# MATRIX_CLOCK.net
KiCad netlist of a schematic drawn in Altium Designer
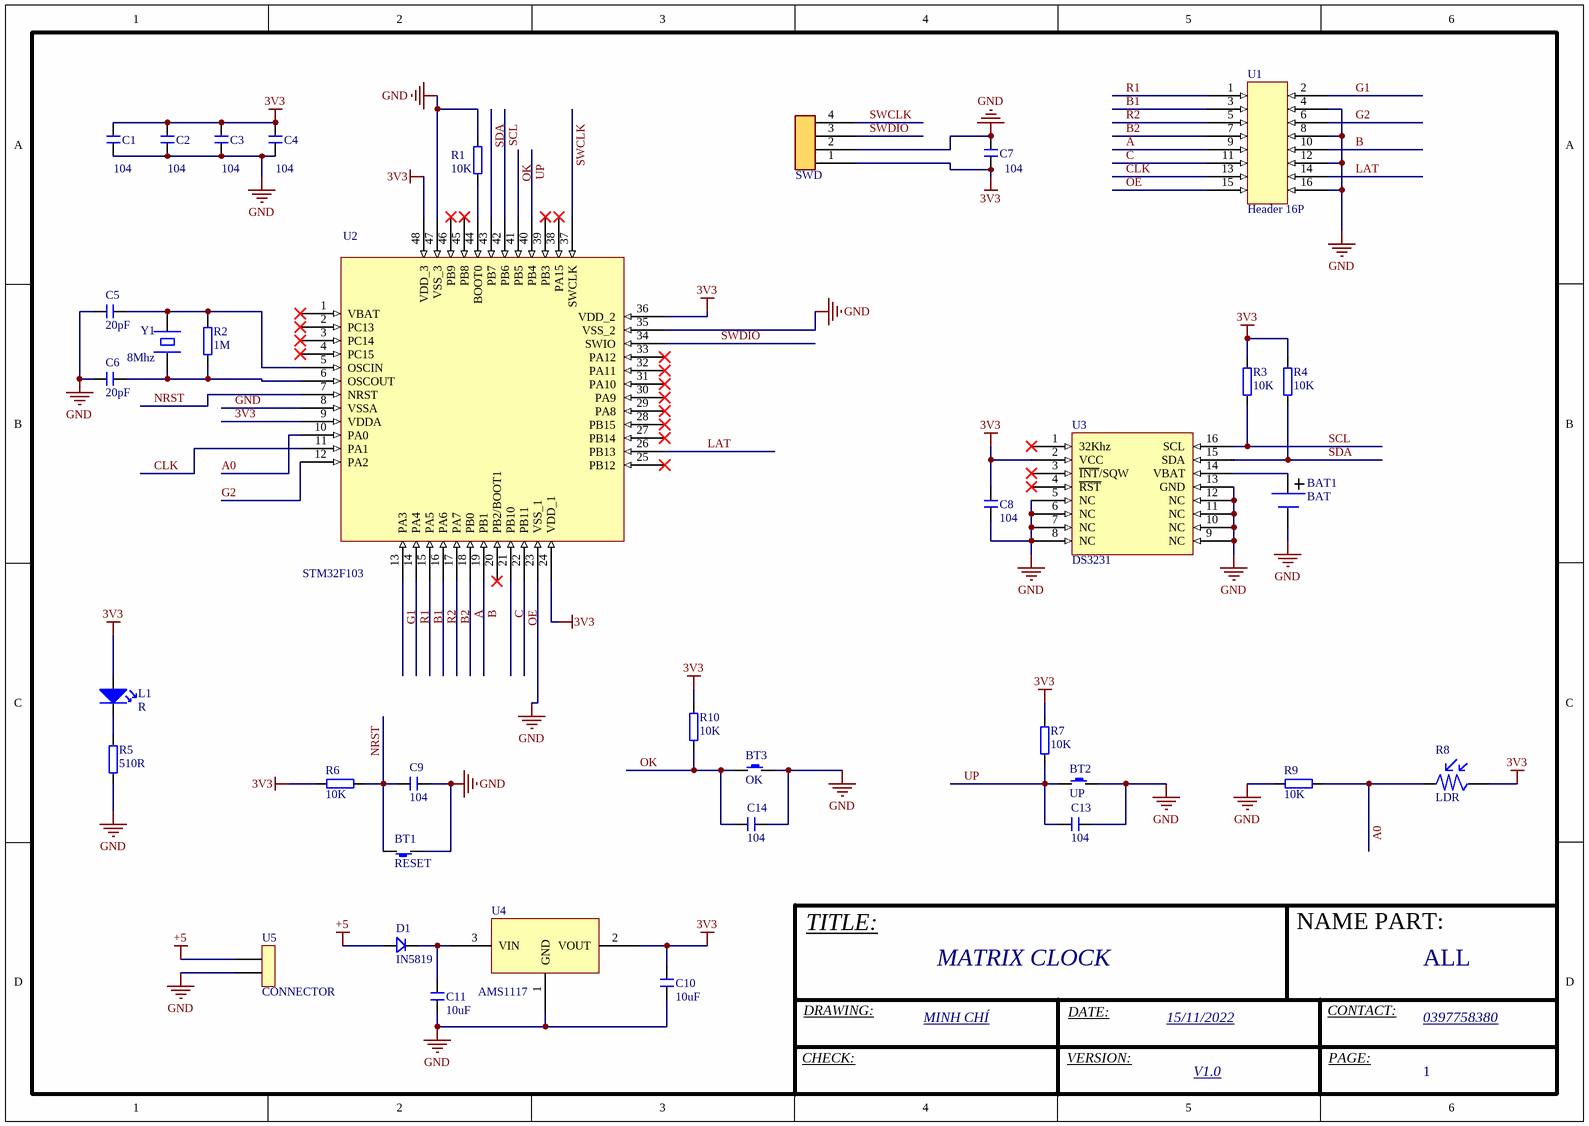
[diagram p0: MATRIX_CLOCK.SchDoc]

(export (version "E")
  (design (tool "Eeschema 10.0.6"))
  (components
    (comp (ref "BAT1")
      (value "BAT")
      (footprint "CR11220")
      (libsource (lib "Lib_MinhChi") (part "BAT_CR1220"))
    )
    (comp (ref "BT1")
      (value "RESET")
      (footprint "BUTTON-2P-SMD")
      (libsource (lib "Lib_MinhChi") (part "BUTON-2P"))
    )
    (comp (ref "BT2")
      (value "UP")
      (footprint "BUTTON-2P-SMD")
      (libsource (lib "Lib_MinhChi") (part "BUTON-2P"))
    )
    (comp (ref "BT3")
      (value "OK")
      (footprint "BUTTON-2P-SMD")
      (libsource (lib "Lib_MinhChi") (part "BUTON-2P"))
    )
    (comp (ref "C1") (value "104") (footprint "CAP-0805") (libsource (lib "Lib_MinhChi") (part "CAP-NON")))
    (comp (ref "C2") (value "104") (footprint "CAP-0805") (libsource (lib "Lib_MinhChi") (part "CAP-NON")))
    (comp (ref "C3") (value "104") (footprint "CAP-0805") (libsource (lib "Lib_MinhChi") (part "CAP-NON")))
    (comp (ref "C4") (value "104") (footprint "CAP-0805") (libsource (lib "Lib_MinhChi") (part "CAP-NON")))
    (comp (ref "C5") (value "20pF") (footprint "CAP-0805") (libsource (lib "Lib_MinhChi") (part "CAP-NON")))
    (comp (ref "C6") (value "20pF") (footprint "CAP-0805") (libsource (lib "Lib_MinhChi") (part "CAP-NON")))
    (comp (ref "C7") (value "104") (footprint "CAP-0805") (libsource (lib "Lib_MinhChi") (part "CAP-NON")))
    (comp (ref "C8") (value "104") (footprint "CAP-0805") (libsource (lib "Lib_MinhChi") (part "CAP-NON")))
    (comp (ref "C9") (value "104") (footprint "CAP-0805") (libsource (lib "Lib_MinhChi") (part "CAP-NON")))
    (comp (ref "C10") (value "10uF") (footprint "CAP-0805") (libsource (lib "Lib_MinhChi") (part "CAP-NON")))
    (comp (ref "C11") (value "10uF") (footprint "CAP-0805") (libsource (lib "Lib_MinhChi") (part "CAP-NON")))
    (comp (ref "C13") (value "104") (footprint "CAP-0805") (libsource (lib "Lib_MinhChi") (part "CAP-NON")))
    (comp (ref "C14") (value "104") (footprint "CAP-0805") (libsource (lib "Lib_MinhChi") (part "CAP-NON")))
    (comp (ref "D1") (value "IN5819") (footprint "IN5819") (libsource (lib "Lib_MinhChi") (part "DIODE")))
    (comp (ref "L1") (value "R") (footprint "LED-R") (libsource (lib "Lib_MinhChi") (part "LED-SINGLE")))
    (comp (ref "R1") (value "10K") (footprint "RES-0805") (libsource (lib "Lib_MinhChi") (part "RES")))
    (comp (ref "R2") (value "1M") (footprint "RES-0805") (libsource (lib "Lib_MinhChi") (part "RES")))
    (comp (ref "R3") (value "10K") (footprint "RES-0805") (libsource (lib "Lib_MinhChi") (part "RES")))
    (comp (ref "R4") (value "10K") (footprint "RES-0805") (libsource (lib "Lib_MinhChi") (part "RES")))
    (comp (ref "R5") (value "510R") (footprint "RES-0805") (libsource (lib "Lib_MinhChi") (part "RES")))
    (comp (ref "R6") (value "10K") (footprint "RES-0805") (libsource (lib "Lib_MinhChi") (part "RES")))
    (comp (ref "R7") (value "10K") (footprint "RES-0805") (libsource (lib "Lib_MinhChi") (part "RES")))
    (comp (ref "R8") (value "LDR") (footprint "LDR2") (libsource (lib "Lib_MinhChi") (part "LDR")))
    (comp (ref "R9") (value "10K") (footprint "RES-0805") (libsource (lib "Lib_MinhChi") (part "RES")))
    (comp (ref "R10") (value "10K") (footprint "RES-0805") (libsource (lib "Lib_MinhChi") (part "RES")))
    (comp (ref "SWD")
      (value "HEADER-4P")
      (footprint "HEADER-4P")
      (libsource (lib "Lib_MinhChi") (part "HEADER-4P"))
    )
    (comp (ref "U1")
      (value "Header 16P")
      (footprint "HEADER16P")
      (libsource (lib "Lib_MinhChi") (part "CONNECTOR 16P"))
    )
    (comp (ref "U2")
      (value "STM32F103")
      (footprint "LQFP-48")
      (libsource (lib "Lib_MinhChi") (part "STM32F103_MCU"))
    )
    (comp (ref "U3") (value "DS3231") (footprint "SOIC16-W") (libsource (lib "Lib_MinhChi") (part "DS3231")))
    (comp (ref "U4")
      (value "AMS1117")
      (footprint "SOT-223")
      (libsource (lib "Lib_MinhChi") (part "AMS1117_SOT-232"))
    )
    (comp (ref "U5") (value "CONNECTOR") (footprint "XH-2P") (libsource (lib "Lib_MinhChi") (part "XH-2P")))
    (comp (ref "Y1") (value "8Mhz") (footprint "QUARTZ") (libsource (lib "Lib_MinhChi") (part "Quartz")))
  )
  (nets
    (net (code "1") (name "+5") (class "Default")
      (node (ref "D1") (pin "1") (pinfunction "A_1") (pintype "passive"))
      (node (ref "U5") (pin "1") (pinfunction "1_1") (pintype "passive"))
    )
    (net (code "2") (name "/A") (class "Default")
      (node (ref "U1") (pin "9") (pintype "input"))
      (node (ref "U2") (pin "18") (pinfunction "PB0_18") (pintype "input"))
    )
    (net (code "3") (name "/A0") (class "Default")
      (node (ref "R8") (pin "1") (pinfunction "1_1") (pintype "passive"))
      (node (ref "R9") (pin "2") (pinfunction "2_2") (pintype "passive"))
      (node (ref "U2") (pin "10") (pinfunction "PA0_10") (pintype "input"))
    )
    (net (code "4") (name "/B") (class "Default")
      (node (ref "U1") (pin "10") (pintype "input"))
      (node (ref "U2") (pin "19") (pinfunction "PB1_19") (pintype "input"))
    )
    (net (code "5") (name "/B1") (class "Default")
      (node (ref "U1") (pin "3") (pintype "input"))
      (node (ref "U2") (pin "15") (pinfunction "PA5_15") (pintype "input"))
    )
    (net (code "6") (name "/B2") (class "Default")
      (node (ref "U1") (pin "7") (pintype "input"))
      (node (ref "U2") (pin "17") (pinfunction "PA7_17") (pintype "input"))
    )
    (net (code "7") (name "/C") (class "Default")
      (node (ref "U1") (pin "11") (pintype "input"))
      (node (ref "U2") (pin "21") (pinfunction "PB10_21") (pintype "input"))
    )
    (net (code "8") (name "/CLK") (class "Default")
      (node (ref "U1") (pin "13") (pintype "input"))
      (node (ref "U2") (pin "11") (pinfunction "PA1_11") (pintype "input"))
    )
    (net (code "9") (name "/G1") (class "Default")
      (node (ref "U1") (pin "2") (pintype "input"))
      (node (ref "U2") (pin "13") (pinfunction "PA3_13") (pintype "input"))
    )
    (net (code "10") (name "/G2") (class "Default")
      (node (ref "U1") (pin "6") (pintype "input"))
      (node (ref "U2") (pin "12") (pinfunction "PA2_12") (pintype "input"))
    )
    (net (code "11") (name "/LAT") (class "Default")
      (node (ref "U1") (pin "14") (pintype "input"))
      (node (ref "U2") (pin "26") (pinfunction "PB13_26") (pintype "input"))
    )
    (net (code "12") (name "/NRST") (class "Default")
      (node (ref "BT1") (pin "2") (pinfunction "2_2") (pintype "passive"))
      (node (ref "C9") (pin "1") (pinfunction "1_1") (pintype "passive"))
      (node (ref "R6") (pin "2") (pinfunction "2_2") (pintype "passive"))
      (node (ref "U2") (pin "7") (pinfunction "NRST_7") (pintype "input"))
    )
    (net (code "13") (name "/OE") (class "Default")
      (node (ref "U1") (pin "15") (pintype "input"))
      (node (ref "U2") (pin "22") (pinfunction "PB11_22") (pintype "input"))
    )
    (net (code "14") (name "/OK") (class "Default")
      (node (ref "BT3") (pin "1") (pinfunction "1_1") (pintype "passive"))
      (node (ref "C14") (pin "1") (pinfunction "1_1") (pintype "passive"))
      (node (ref "R10") (pin "2") (pinfunction "2_2") (pintype "passive"))
      (node (ref "U2") (pin "41") (pinfunction "PB5_41") (pintype "input"))
    )
    (net (code "15") (name "/R1") (class "Default")
      (node (ref "U1") (pin "1") (pintype "input"))
      (node (ref "U2") (pin "14") (pinfunction "PA4_14") (pintype "input"))
    )
    (net (code "16") (name "/R2") (class "Default")
      (node (ref "U1") (pin "5") (pintype "input"))
      (node (ref "U2") (pin "16") (pinfunction "PA6_16") (pintype "input"))
    )
    (net (code "17") (name "/SCL") (class "Default")
      (node (ref "R3") (pin "1") (pinfunction "1_1") (pintype "passive"))
      (node (ref "U2") (pin "42") (pinfunction "PB6_42") (pintype "input"))
      (node (ref "U3") (pin "16") (pinfunction "SCL_16") (pintype "input"))
    )
    (net (code "18") (name "/SDA") (class "Default")
      (node (ref "R4") (pin "1") (pinfunction "1_1") (pintype "passive"))
      (node (ref "U2") (pin "43") (pinfunction "PB7_43") (pintype "input"))
      (node (ref "U3") (pin "15") (pinfunction "SDA_15") (pintype "input"))
    )
    (net (code "19") (name "/SWCLK") (class "Default")
      (node (ref "SWD") (pin "4") (pinfunction "4_4") (pintype "passive"))
      (node (ref "U2") (pin "37") (pinfunction "SWCLK_37") (pintype "input"))
    )
    (net (code "20") (name "/SWDIO") (class "Default")
      (node (ref "SWD") (pin "3") (pinfunction "3_3") (pintype "passive"))
      (node (ref "U2") (pin "34") (pinfunction "SWIO_34") (pintype "input"))
    )
    (net (code "21") (name "/UP") (class "Default")
      (node (ref "BT2") (pin "1") (pinfunction "1_1") (pintype "passive"))
      (node (ref "C13") (pin "1") (pinfunction "1_1") (pintype "passive"))
      (node (ref "R7") (pin "2") (pinfunction "2_2") (pintype "passive"))
      (node (ref "U2") (pin "40") (pinfunction "PB4_40") (pintype "input"))
    )
    (net (code "22") (name "3V3") (class "Default")
      (node (ref "C1") (pin "1") (pinfunction "1_1") (pintype "passive"))
      (node (ref "C10") (pin "1") (pinfunction "1_1") (pintype "passive"))
      (node (ref "C2") (pin "1") (pinfunction "1_1") (pintype "passive"))
      (node (ref "C3") (pin "1") (pinfunction "1_1") (pintype "passive"))
      (node (ref "C4") (pin "1") (pinfunction "1_1") (pintype "passive"))
      (node (ref "C7") (pin "2") (pinfunction "2_2") (pintype "passive"))
      (node (ref "C8") (pin "1") (pinfunction "1_1") (pintype "passive"))
      (node (ref "L1") (pin "1") (pinfunction "1_1") (pintype "passive"))
      (node (ref "R10") (pin "1") (pinfunction "1_1") (pintype "passive"))
      (node (ref "R3") (pin "2") (pinfunction "2_2") (pintype "passive"))
      (node (ref "R4") (pin "2") (pinfunction "2_2") (pintype "passive"))
      (node (ref "R6") (pin "1") (pinfunction "1_1") (pintype "passive"))
      (node (ref "R7") (pin "1") (pinfunction "1_1") (pintype "passive"))
      (node (ref "R8") (pin "1") (pinfunction "1_1") (pintype "passive"))
      (node (ref "SWD") (pin "1") (pinfunction "1_1") (pintype "passive"))
      (node (ref "U2") (pin "24") (pinfunction "VDD_1_24") (pintype "input"))
      (node (ref "U2") (pin "36") (pinfunction "VDD_2_36") (pintype "input"))
      (node (ref "U2") (pin "48") (pinfunction "VDD_3_48") (pintype "input"))
      (node (ref "U2") (pin "9") (pinfunction "VDDA_9") (pintype "input"))
      (node (ref "U3") (pin "2") (pinfunction "VCC_2") (pintype "input"))
      (node (ref "U4") (pin "2") (pinfunction "VOUT_2") (pintype "passive"))
    )
    (net (code "23") (name "GND") (class "Default")
      (node (ref "BAT1") (pin "2") (pinfunction "2_2") (pintype "passive"))
      (node (ref "BT1") (pin "1") (pinfunction "1_1") (pintype "passive"))
      (node (ref "BT2") (pin "2") (pinfunction "2_2") (pintype "passive"))
      (node (ref "BT3") (pin "2") (pinfunction "2_2") (pintype "passive"))
      (node (ref "C1") (pin "2") (pinfunction "2_2") (pintype "passive"))
      (node (ref "C10") (pin "2") (pinfunction "2_2") (pintype "passive"))
      (node (ref "C11") (pin "2") (pinfunction "2_2") (pintype "passive"))
      (node (ref "C13") (pin "2") (pinfunction "2_2") (pintype "passive"))
      (node (ref "C14") (pin "2") (pinfunction "2_2") (pintype "passive"))
      (node (ref "C2") (pin "2") (pinfunction "2_2") (pintype "passive"))
      (node (ref "C3") (pin "2") (pinfunction "2_2") (pintype "passive"))
      (node (ref "C4") (pin "2") (pinfunction "2_2") (pintype "passive"))
      (node (ref "C5") (pin "2") (pinfunction "2_2") (pintype "passive"))
      (node (ref "C6") (pin "2") (pinfunction "2_2") (pintype "passive"))
      (node (ref "C7") (pin "1") (pinfunction "1_1") (pintype "passive"))
      (node (ref "C8") (pin "2") (pinfunction "2_2") (pintype "passive"))
      (node (ref "C9") (pin "2") (pinfunction "2_2") (pintype "passive"))
      (node (ref "R1") (pin "1") (pinfunction "1_1") (pintype "passive"))
      (node (ref "R5") (pin "1") (pinfunction "1_1") (pintype "passive"))
      (node (ref "R9") (pin "1") (pinfunction "1_1") (pintype "passive"))
      (node (ref "SWD") (pin "2") (pinfunction "2_2") (pintype "passive"))
      (node (ref "U1") (pin "12") (pintype "input"))
      (node (ref "U1") (pin "16") (pintype "input"))
      (node (ref "U1") (pin "4") (pintype "input"))
      (node (ref "U1") (pin "8") (pintype "input"))
      (node (ref "U2") (pin "23") (pinfunction "VSS_1_23") (pintype "input"))
      (node (ref "U2") (pin "35") (pinfunction "VSS_2_35") (pintype "input"))
      (node (ref "U2") (pin "47") (pinfunction "VSS_3_47") (pintype "input"))
      (node (ref "U2") (pin "8") (pinfunction "VSSA_8") (pintype "input"))
      (node (ref "U3") (pin "10") (pinfunction "NC_10") (pintype "input"))
      (node (ref "U3") (pin "11") (pinfunction "NC_11") (pintype "input"))
      (node (ref "U3") (pin "12") (pinfunction "NC_12") (pintype "input"))
      (node (ref "U3") (pin "13") (pinfunction "GND_13") (pintype "input"))
      (node (ref "U3") (pin "5") (pinfunction "NC_5") (pintype "input"))
      (node (ref "U3") (pin "6") (pinfunction "NC_6") (pintype "input"))
      (node (ref "U3") (pin "7") (pinfunction "NC_7") (pintype "input"))
      (node (ref "U3") (pin "8") (pinfunction "NC_8") (pintype "input"))
      (node (ref "U3") (pin "9") (pinfunction "NC_9") (pintype "input"))
      (node (ref "U4") (pin "1") (pinfunction "GND_1") (pintype "passive"))
      (node (ref "U5") (pin "2") (pinfunction "2_2") (pintype "passive"))
    )
    (net (code "24") (name "Net-(D1-K)") (class "Default")
      (node (ref "C11") (pin "1") (pinfunction "1_1") (pintype "passive"))
      (node (ref "D1") (pin "2") (pinfunction "K_2") (pintype "passive"))
      (node (ref "U4") (pin "3") (pinfunction "VIN_3") (pintype "passive"))
    )
    (net (code "25") (name "Net-(L1-Pad2)") (class "Default")
      (node (ref "L1") (pin "2") (pinfunction "2_2") (pintype "passive"))
      (node (ref "R5") (pin "2") (pinfunction "2_2") (pintype "passive"))
    )
    (net (code "26") (name "Net-(U2-BOOT0)") (class "Default")
      (node (ref "R1") (pin "2") (pinfunction "2_2") (pintype "passive"))
      (node (ref "U2") (pin "44") (pinfunction "BOOT0_44") (pintype "input"))
    )
    (net (code "27") (name "Net-(U2-OSCIN)") (class "Default")
      (node (ref "C5") (pin "1") (pinfunction "1_1") (pintype "passive"))
      (node (ref "R2") (pin "2") (pinfunction "2_2") (pintype "passive"))
      (node (ref "U2") (pin "5") (pinfunction "OSCIN_5") (pintype "input"))
      (node (ref "Y1") (pin "2") (pinfunction "2_2") (pintype "passive"))
    )
    (net (code "28") (name "Net-(U2-OSCOUT)") (class "Default")
      (node (ref "C6") (pin "1") (pinfunction "1_1") (pintype "passive"))
      (node (ref "R2") (pin "1") (pinfunction "1_1") (pintype "passive"))
      (node (ref "U2") (pin "6") (pinfunction "OSCOUT_6") (pintype "input"))
      (node (ref "Y1") (pin "1") (pinfunction "4_1") (pintype "passive"))
    )
    (net (code "29") (name "Net-(U3-VBAT)") (class "Default")
      (node (ref "BAT1") (pin "1") (pinfunction "1_1") (pintype "passive"))
      (node (ref "U3") (pin "14") (pinfunction "VBAT_14") (pintype "input"))
    )
    (net (code "30") (name "unconnected-(U2-PA8-Pad29)") (class "Default")
      (node (ref "U2") (pin "29") (pinfunction "PA8_29") (pintype "input+no_connect"))
    )
    (net (code "31") (name "unconnected-(U2-PA9-Pad30)") (class "Default")
      (node (ref "U2") (pin "30") (pinfunction "PA9_30") (pintype "input+no_connect"))
    )
    (net (code "32") (name "unconnected-(U2-PA10-Pad31)") (class "Default")
      (node (ref "U2") (pin "31") (pinfunction "PA10_31") (pintype "input+no_connect"))
    )
    (net (code "33") (name "unconnected-(U2-PA11-Pad32)") (class "Default")
      (node (ref "U2") (pin "32") (pinfunction "PA11_32") (pintype "input+no_connect"))
    )
    (net (code "34") (name "unconnected-(U2-PA12-Pad33)") (class "Default")
      (node (ref "U2") (pin "33") (pinfunction "PA12_33") (pintype "input+no_connect"))
    )
    (net (code "35") (name "unconnected-(U2-PA15-Pad38)") (class "Default")
      (node (ref "U2") (pin "38") (pinfunction "PA15_38") (pintype "input+no_connect"))
    )
    (net (code "36") (name "unconnected-(U2-PB2{slash}BOOT1-Pad20)") (class "Default")
      (node (ref "U2") (pin "20") (pinfunction "PB2/BOOT1_20") (pintype "input+no_connect"))
    )
    (net (code "37") (name "unconnected-(U2-PB3-Pad39)") (class "Default")
      (node (ref "U2") (pin "39") (pinfunction "PB3_39") (pintype "input+no_connect"))
    )
    (net (code "38") (name "unconnected-(U2-PB8-Pad45)") (class "Default")
      (node (ref "U2") (pin "45") (pinfunction "PB8_45") (pintype "input+no_connect"))
    )
    (net (code "39") (name "unconnected-(U2-PB9-Pad46)") (class "Default")
      (node (ref "U2") (pin "46") (pinfunction "PB9_46") (pintype "input+no_connect"))
    )
    (net (code "40") (name "unconnected-(U2-PB12-Pad25)") (class "Default")
      (node (ref "U2") (pin "25") (pinfunction "PB12_25") (pintype "input+no_connect"))
    )
    (net (code "41") (name "unconnected-(U2-PB14-Pad27)") (class "Default")
      (node (ref "U2") (pin "27") (pinfunction "PB14_27") (pintype "input+no_connect"))
    )
    (net (code "42") (name "unconnected-(U2-PB15-Pad28)") (class "Default")
      (node (ref "U2") (pin "28") (pinfunction "PB15_28") (pintype "input+no_connect"))
    )
    (net (code "43") (name "unconnected-(U2-PC13-Pad2)") (class "Default")
      (node (ref "U2") (pin "2") (pinfunction "PC13_2") (pintype "input+no_connect"))
    )
    (net (code "44") (name "unconnected-(U2-PC14-Pad3)") (class "Default")
      (node (ref "U2") (pin "3") (pinfunction "PC14_3") (pintype "input+no_connect"))
    )
    (net (code "45") (name "unconnected-(U2-PC15-Pad4)") (class "Default")
      (node (ref "U2") (pin "4") (pinfunction "PC15_4") (pintype "input+no_connect"))
    )
    (net (code "46") (name "unconnected-(U2-VBAT-Pad1)") (class "Default")
      (node (ref "U2") (pin "1") (pinfunction "VBAT_1") (pintype "input+no_connect"))
    )
    (net (code "47") (name "unconnected-(U3-32Khz-Pad1)") (class "Default")
      (node (ref "U3") (pin "1") (pinfunction "32Khz_1") (pintype "input+no_connect"))
    )
    (net (code "48") (name "unconnected-(U3-~{INT}{slash}SQW-Pad3)") (class "Default")
      (node (ref "U3") (pin "3") (pinfunction "~{INT}/SQW_3") (pintype "input+no_connect"))
    )
    (net (code "49") (name "unconnected-(U3-~{RST}-Pad4)") (class "Default")
      (node (ref "U3") (pin "4") (pinfunction "~{RST}_4") (pintype "input+no_connect"))
    )
  )
)
